# Sheet_1_2023-07-02.net
KiCad netlist of a schematic drawn in Altium Designer
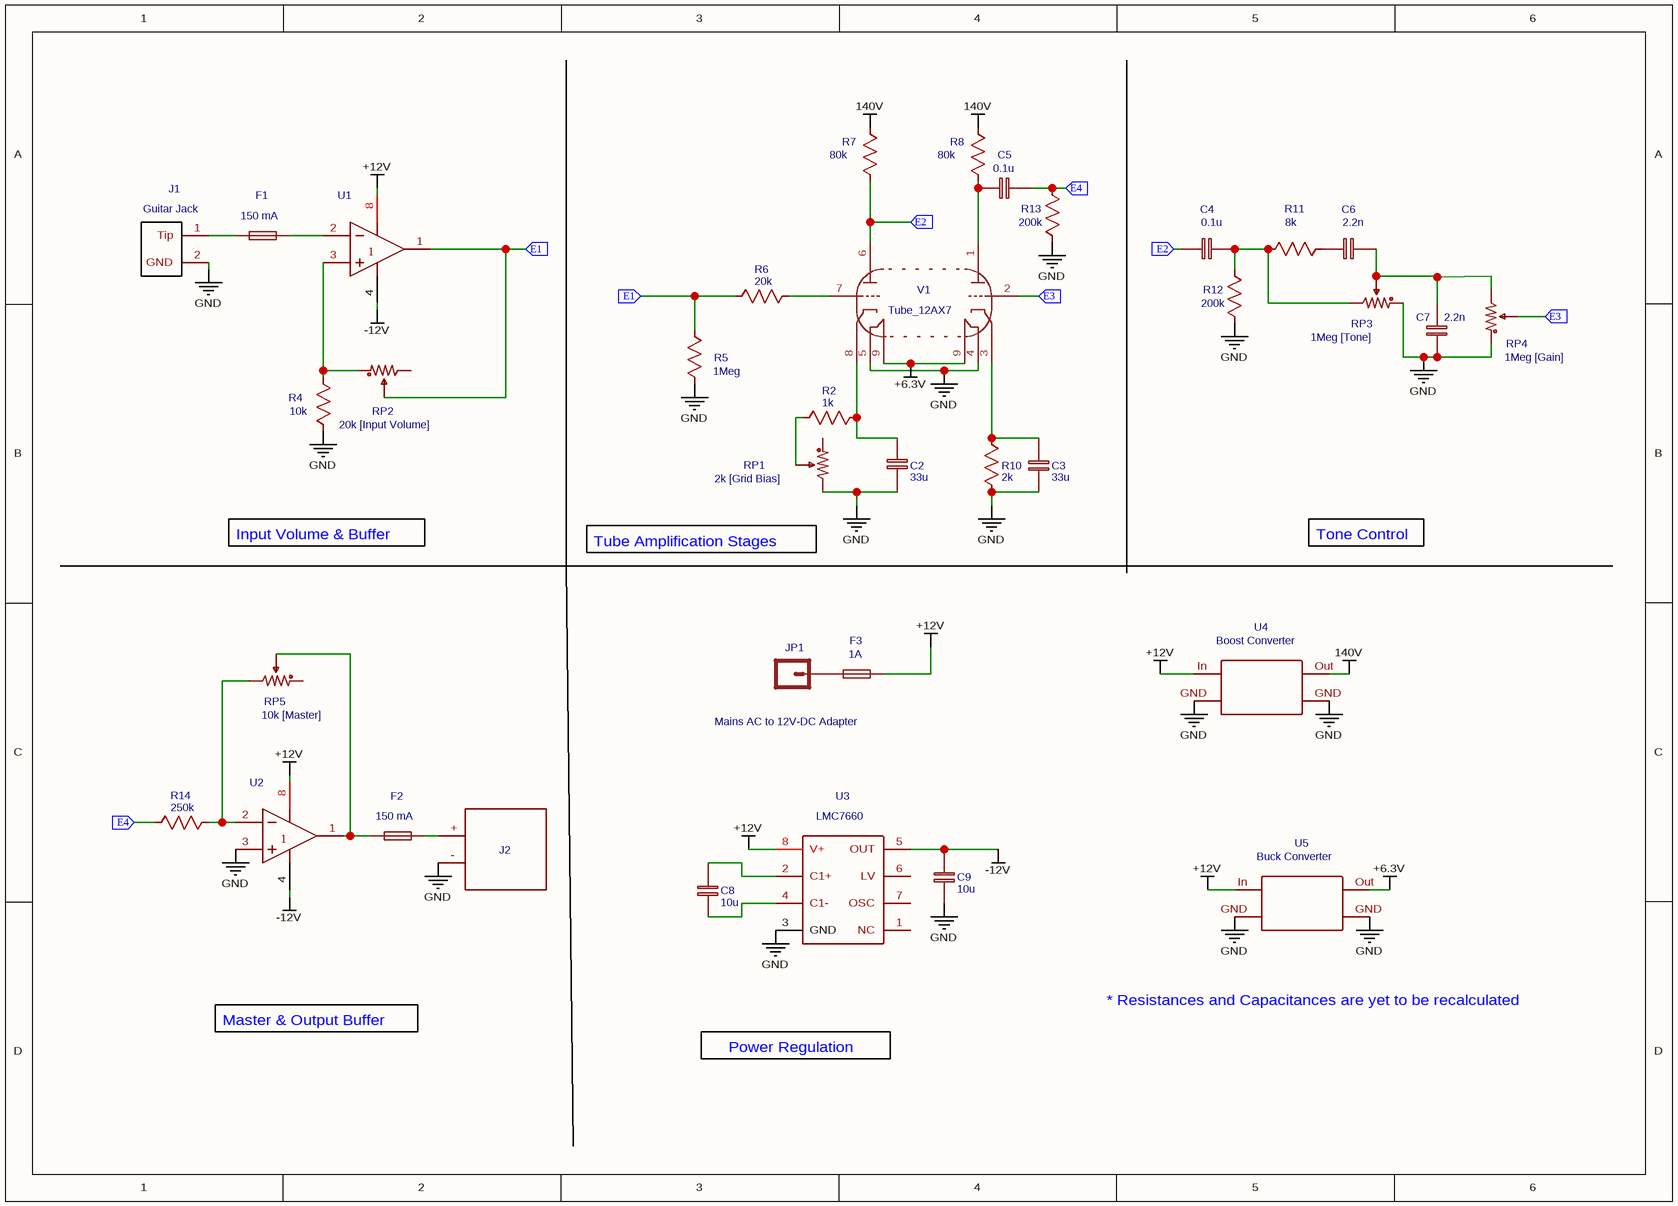
[diagram p0: Sheet_1_2023-07-02.schdoc]

(export (version "E")
  (design (tool "Eeschema 10.0.6"))
  (components
    (comp (ref "C2")
      (value "33u")
      (fields (field (name "CONTRIBUTOR") "LCEDA_Lib"))
      (libsource (lib "altium-import") (part "root_3_33u_"))
    )
    (comp (ref "C3")
      (value "33u")
      (fields (field (name "CONTRIBUTOR") "LCEDA_Lib"))
      (libsource (lib "altium-import") (part "root_1_33u_"))
    )
    (comp (ref "C4")
      (value "0.1u")
      (fields (field (name "CONTRIBUTOR") "LCEDA_Lib"))
      (libsource (lib "altium-import") (part "root_0_0.1u_"))
    )
    (comp (ref "C5")
      (value "0.1u")
      (fields (field (name "CONTRIBUTOR") "LCEDA_Lib"))
      (libsource (lib "altium-import") (part "root_0_0.1u_"))
    )
    (comp (ref "C6")
      (value "2.2n")
      (fields (field (name "CONTRIBUTOR") "LCEDA_Lib"))
      (libsource (lib "altium-import") (part "root_0_2.2n_"))
    )
    (comp (ref "C7")
      (value "2.2n")
      (fields (field (name "CONTRIBUTOR") "LCEDA_Lib"))
      (libsource (lib "altium-import") (part "root_1_2.2n_"))
    )
    (comp (ref "C8")
      (value "10u")
      (fields (field (name "CONTRIBUTOR") "LCEDA_Lib"))
      (libsource (lib "altium-import") (part "root_1_10u_"))
    )
    (comp (ref "C9")
      (value "10u")
      (fields (field (name "CONTRIBUTOR") "LCEDA_Lib"))
      (libsource (lib "altium-import") (part "root_1_10u_"))
    )
    (comp (ref "F1") (value "150 mA") (libsource (lib "altium-import") (part "root_0_150 mA_")))
    (comp (ref "F2") (value "150 mA") (libsource (lib "altium-import") (part "root_0_150 mA_")))
    (comp (ref "F3") (value "1A") (libsource (lib "altium-import") (part "root_0_1A_")))
    (comp (ref "J1")
      (value "Guitar Jack")
      (fields (field (name "CONTRIBUTOR") "Jose Tovar"))
      (libsource (lib "altium-import") (part "root_0_Guitar Jack_"))
    )
    (comp (ref "J2")
      (value "Guitar_Jack_Output")
      (fields (field (name "CONTRIBUTOR") "ahmits"))
      (libsource (lib "altium-import") (part "root_0_Guitar_Jack_Output_"))
    )
    (comp (ref "JP1")
      (value "Mains AC to 12V-DC Adapter")
      (fields (field (name "CONTRIBUTOR") "SparkFun"))
      (libsource (lib "altium-import") (part "root_0_Mains AC to 12V-DC Adapter_"))
    )
    (comp (ref "R2")
      (value "1k")
      (fields (field (name "CONTRIBUTOR") "LCEDA_Lib"))
      (libsource (lib "altium-import") (part "root_2_1k_"))
    )
    (comp (ref "R4")
      (value "10k")
      (fields (field (name "CONTRIBUTOR") "LCEDA_Lib"))
      (libsource (lib "altium-import") (part "root_1_10k_"))
    )
    (comp (ref "R5")
      (value "1Meg")
      (fields (field (name "CONTRIBUTOR") "LCEDA_Lib"))
      (libsource (lib "altium-import") (part "root_1_1Meg_"))
    )
    (comp (ref "R6")
      (value "20k")
      (fields (field (name "CONTRIBUTOR") "LCEDA_Lib"))
      (libsource (lib "altium-import") (part "root_2_20k_"))
    )
    (comp (ref "R7")
      (value "80k")
      (fields (field (name "CONTRIBUTOR") "LCEDA_Lib"))
      (libsource (lib "altium-import") (part "root_3_80k_"))
    )
    (comp (ref "R8")
      (value "80k")
      (fields (field (name "CONTRIBUTOR") "LCEDA_Lib"))
      (libsource (lib "altium-import") (part "root_3_80k_"))
    )
    (comp (ref "R10")
      (value "2k")
      (fields (field (name "CONTRIBUTOR") "LCEDA_Lib"))
      (libsource (lib "altium-import") (part "root_3_2k_"))
    )
    (comp (ref "R11")
      (value "8k")
      (fields (field (name "CONTRIBUTOR") "LCEDA_Lib"))
      (libsource (lib "altium-import") (part "root_2_8k_"))
    )
    (comp (ref "R12")
      (value "200k")
      (fields (field (name "CONTRIBUTOR") "LCEDA_Lib"))
      (libsource (lib "altium-import") (part "root_3_200k_"))
    )
    (comp (ref "R13")
      (value "200k")
      (fields (field (name "CONTRIBUTOR") "LCEDA_Lib"))
      (libsource (lib "altium-import") (part "root_3_200k_"))
    )
    (comp (ref "R14")
      (value "250k")
      (fields (field (name "CONTRIBUTOR") "LCEDA_Lib"))
      (libsource (lib "altium-import") (part "root_2_250k_"))
    )
    (comp (ref "RP1")
      (value "2k [Grid Bias]")
      (fields (field (name "CONTRIBUTOR") "LCEDA_Lib"))
      (libsource (lib "altium-import") (part "root_1_2k [Grid Bias]_"))
    )
    (comp (ref "RP2")
      (value "20k [Input Volume]")
      (fields (field (name "CONTRIBUTOR") "LCEDA_Lib"))
      (libsource (lib "altium-import") (part "root_2_20k [Input Volume]_"))
    )
    (comp (ref "RP3")
      (value "1Meg [Tone]")
      (fields (field (name "CONTRIBUTOR") "LCEDA_Lib"))
      (libsource (lib "altium-import") (part "root_0_1Meg [Tone]_"))
    )
    (comp (ref "RP4")
      (value "1Meg [Gain]")
      (fields (field (name "CONTRIBUTOR") "LCEDA_Lib"))
      (libsource (lib "altium-import") (part "root_3_1Meg [Gain]_"))
    )
    (comp (ref "RP5")
      (value "10k [Master]")
      (fields (field (name "CONTRIBUTOR") "LCEDA_Lib"))
      (libsource (lib "altium-import") (part "root_0_10k [Master]_"))
    )
    (comp (ref "U1")
      (value "HA7-5102-2")
      (description "Low Noise Operational Amplifier")
      (fields (field (name "SUBPART_NO") "1"))
      (libsource (lib "altium-import") (part "root_0_HA7-5102-2_"))
    )
    (comp (ref "U2")
      (value "HA7-5102-2")
      (description "Low Noise Operational Amplifier")
      (fields (field (name "SUBPART_NO") "1"))
      (libsource (lib "altium-import") (part "root_0_HA7-5102-2_"))
    )
    (comp (ref "U3")
      (value "LMC7660")
      (description "Switched Capacitor Voltage Converter, 8-pin MDIP, Pb-Free")
      (libsource (lib "altium-import") (part "root_0_LMC7660_"))
    )
    (comp (ref "U4")
      (value "Boost Converter")
      (description "800mA Low-Dropout Linear Regulator, 4-pin SOT-223, Pb-Free")
      (libsource (lib "altium-import") (part "root_0_Boost Converter_"))
    )
    (comp (ref "U5")
      (value "Buck Converter")
      (description "800mA Low-Dropout Linear Regulator, 4-pin SOT-223, Pb-Free")
      (libsource (lib "altium-import") (part "root_0_Buck Converter_"))
    )
    (comp (ref "V1")
      (value "Tube_12AX7")
      (description "High Mu Dual Triode")
      (fields (field (name "CONTRIBUTOR") "prvi sedmi"))
      (libsource (lib "altium-import") (part "root_0_Tube_12AX7_"))
    )
  )
  (nets
    (net (code "1") (name "+6.3V") (class "Default")
      (node (ref "U5") (pin "Out") (pinfunction "OUT_Out") (pintype "passive"))
      (node (ref "V1") (pin "9") (pinfunction "HM_9") (pintype "passive"))
    )
    (net (code "2") (name "+12V") (class "Default")
      (node (ref "F3") (pin "2") (pinfunction "2_2") (pintype "passive"))
      (node (ref "U1") (pin "8") (pinfunction "V+_8") (pintype "passive"))
      (node (ref "U2") (pin "8") (pinfunction "V+_8") (pintype "passive"))
      (node (ref "U3") (pin "8") (pinfunction "V+_8") (pintype "passive"))
      (node (ref "U4") (pin "In") (pinfunction "IN_In") (pintype "passive"))
      (node (ref "U5") (pin "In") (pinfunction "IN_In") (pintype "passive"))
    )
    (net (code "3") (name "-12V") (class "Default")
      (node (ref "C9") (pin "2") (pinfunction "2_2") (pintype "passive"))
      (node (ref "U1") (pin "4") (pinfunction "V-_4") (pintype "passive"))
      (node (ref "U2") (pin "4") (pinfunction "V-_4") (pintype "passive"))
      (node (ref "U3") (pin "5") (pinfunction "OUT_5") (pintype "passive"))
    )
    (net (code "4") (name "/E1") (class "Default")
      (node (ref "R5") (pin "2") (pinfunction "2_2") (pintype "passive"))
      (node (ref "R6") (pin "2") (pinfunction "2_2") (pintype "passive"))
      (node (ref "RP2") (pin "2") (pinfunction "2_2") (pintype "passive"))
      (node (ref "U1") (pin "1") (pinfunction "OUT_1") (pintype "passive"))
    )
    (net (code "5") (name "/E2") (class "Default")
      (node (ref "C4") (pin "1") (pinfunction "1_1") (pintype "passive"))
      (node (ref "R7") (pin "2") (pinfunction "2_2") (pintype "passive"))
      (node (ref "V1") (pin "6") (pinfunction "PT2_6") (pintype "passive"))
    )
    (net (code "6") (name "/E3") (class "Default")
      (node (ref "RP4") (pin "2") (pinfunction "2_2") (pintype "passive"))
      (node (ref "V1") (pin "2") (pinfunction "GT1_2") (pintype "passive"))
    )
    (net (code "7") (name "/E4") (class "Default")
      (node (ref "C5") (pin "2") (pinfunction "2_2") (pintype "passive"))
      (node (ref "R13") (pin "1") (pinfunction "1_1") (pintype "passive"))
      (node (ref "R14") (pin "2") (pinfunction "2_2") (pintype "passive"))
    )
    (net (code "8") (name "140V") (class "Default")
      (node (ref "R7") (pin "1") (pinfunction "1_1") (pintype "passive"))
      (node (ref "R8") (pin "1") (pinfunction "1_1") (pintype "passive"))
      (node (ref "U4") (pin "Out") (pinfunction "OUT_Out") (pintype "passive"))
    )
    (net (code "9") (name "GND") (class "Default")
      (node (ref "C2") (pin "2") (pinfunction "2_2") (pintype "passive"))
      (node (ref "C3") (pin "1") (pinfunction "1_1") (pintype "passive"))
      (node (ref "C7") (pin "1") (pinfunction "1_1") (pintype "passive"))
      (node (ref "C9") (pin "1") (pinfunction "1_1") (pintype "passive"))
      (node (ref "J1") (pin "2") (pinfunction "GND_2") (pintype "passive"))
      (node (ref "R10") (pin "2") (pinfunction "2_2") (pintype "passive"))
      (node (ref "R12") (pin "2") (pinfunction "2_2") (pintype "passive"))
      (node (ref "R13") (pin "2") (pinfunction "2_2") (pintype "passive"))
      (node (ref "R4") (pin "1") (pinfunction "1_1") (pintype "passive"))
      (node (ref "R5") (pin "1") (pinfunction "1_1") (pintype "passive"))
      (node (ref "RP1") (pin "3") (pinfunction "3_3") (pintype "passive"))
      (node (ref "RP3") (pin "1") (pinfunction "1_1") (pintype "passive"))
      (node (ref "RP4") (pin "1") (pinfunction "1_1") (pintype "passive"))
      (node (ref "U2") (pin "3") (pinfunction "IN+_3") (pintype "passive"))
      (node (ref "U3") (pin "3") (pinfunction "GND_3") (pintype "passive"))
      (node (ref "U4") (pin "GND") (pinfunction "ADJ_GND") (pintype "passive"))
      (node (ref "U5") (pin "GND") (pinfunction "TAB_GND") (pintype "passive"))
      (node (ref "V1") (pin "4") (pinfunction "H_4") (pintype "passive"))
      (node (ref "V1") (pin "5") (pinfunction "H_5") (pintype "passive"))
    )
    (net (code "10") (name "Net-(C4-Pad2)") (class "Default")
      (node (ref "C4") (pin "2") (pinfunction "2_2") (pintype "passive"))
      (node (ref "R11") (pin "2") (pinfunction "2_2") (pintype "passive"))
      (node (ref "R12") (pin "1") (pinfunction "1_1") (pintype "passive"))
      (node (ref "RP3") (pin "3") (pinfunction "3_3") (pintype "passive"))
    )
    (net (code "11") (name "Net-(C6-Pad1)") (class "Default")
      (node (ref "C6") (pin "1") (pinfunction "1_1") (pintype "passive"))
      (node (ref "R11") (pin "1") (pinfunction "1_1") (pintype "passive"))
    )
    (net (code "12") (name "Net-(C6-Pad2)") (class "Default")
      (node (ref "C6") (pin "2") (pinfunction "2_2") (pintype "passive"))
      (node (ref "C7") (pin "2") (pinfunction "2_2") (pintype "passive"))
      (node (ref "RP3") (pin "2") (pinfunction "2_2") (pintype "passive"))
      (node (ref "RP4") (pin "3") (pinfunction "3_3") (pintype "passive"))
    )
    (net (code "13") (name "Net-(J1-Tip)") (class "Default")
      (node (ref "F1") (pin "1") (pinfunction "1_1") (pintype "passive"))
      (node (ref "J1") (pin "1") (pinfunction "Tip_1") (pintype "passive"))
    )
    (net (code "14") (name "Net-(JP1-1)") (class "Default")
      (node (ref "F3") (pin "1") (pinfunction "1_1") (pintype "passive"))
      (node (ref "JP1") (pin "P$2") (pinfunction "1_P$2") (pintype "passive"))
    )
    (net (code "15") (name "Net-(R2-Pad2)") (class "Default")
      (node (ref "R2") (pin "2") (pinfunction "2_2") (pintype "passive"))
      (node (ref "RP1") (pin "2") (pinfunction "2_2") (pintype "passive"))
    )
    (net (code "16") (name "Net-(U1-IN+)") (class "Default")
      (node (ref "R4") (pin "2") (pinfunction "2_2") (pintype "passive"))
      (node (ref "RP2") (pin "1") (pinfunction "1_1") (pintype "passive"))
      (node (ref "U1") (pin "3") (pinfunction "IN+_3") (pintype "passive"))
    )
    (net (code "17") (name "Net-(U1-IN-)") (class "Default")
      (node (ref "F1") (pin "2") (pinfunction "2_2") (pintype "passive"))
      (node (ref "U1") (pin "2") (pinfunction "IN-_2") (pintype "passive"))
    )
    (net (code "18") (name "Net-(U2-IN-)") (class "Default")
      (node (ref "R14") (pin "1") (pinfunction "1_1") (pintype "passive"))
      (node (ref "RP5") (pin "3") (pinfunction "3_3") (pintype "passive"))
      (node (ref "U2") (pin "2") (pinfunction "IN-_2") (pintype "passive"))
    )
    (net (code "19") (name "Net-(U2-OUT)") (class "Default")
      (node (ref "F2") (pin "1") (pinfunction "1_1") (pintype "passive"))
      (node (ref "RP5") (pin "2") (pinfunction "2_2") (pintype "passive"))
      (node (ref "U2") (pin "1") (pinfunction "OUT_1") (pintype "passive"))
    )
    (net (code "20") (name "Net-(U3-C1+)") (class "Default")
      (node (ref "C8") (pin "2") (pinfunction "2_2") (pintype "passive"))
      (node (ref "U3") (pin "2") (pinfunction "C1+_2") (pintype "passive"))
    )
    (net (code "21") (name "Net-(U3-C1-)") (class "Default")
      (node (ref "C8") (pin "1") (pinfunction "1_1") (pintype "passive"))
      (node (ref "U3") (pin "4") (pinfunction "C1-_4") (pintype "passive"))
    )
    (net (code "22") (name "Net-(V1-GT2)") (class "Default")
      (node (ref "R6") (pin "1") (pinfunction "1_1") (pintype "passive"))
      (node (ref "V1") (pin "7") (pinfunction "GT2_7") (pintype "passive"))
    )
    (net (code "23") (name "Net-(V1-KT1)") (class "Default")
      (node (ref "C3") (pin "2") (pinfunction "2_2") (pintype "passive"))
      (node (ref "R10") (pin "1") (pinfunction "1_1") (pintype "passive"))
      (node (ref "V1") (pin "3") (pinfunction "KT1_3") (pintype "passive"))
    )
    (net (code "24") (name "Net-(V1-KT2)") (class "Default")
      (node (ref "C2") (pin "1") (pinfunction "1_1") (pintype "passive"))
      (node (ref "R2") (pin "1") (pinfunction "1_1") (pintype "passive"))
      (node (ref "V1") (pin "8") (pinfunction "KT2_8") (pintype "passive"))
    )
    (net (code "25") (name "Net-(V1-PT1)") (class "Default")
      (node (ref "C5") (pin "1") (pinfunction "1_1") (pintype "passive"))
      (node (ref "R8") (pin "2") (pinfunction "2_2") (pintype "passive"))
      (node (ref "V1") (pin "1") (pinfunction "PT1_1") (pintype "passive"))
    )
    (net (code "26") (name "unconnected-(F2-Pad2)") (class "Default")
      (node (ref "F2") (pin "2") (pinfunction "2_2") (pintype "passive"))
    )
    (net (code "27") (name "unconnected-(J2-1-Pad+)") (class "Default")
      (node (ref "J2") (pin "+") (pinfunction "1_+") (pintype "passive"))
    )
    (net (code "28") (name "unconnected-(J2-2-Pad-)") (class "Default")
      (node (ref "J2") (pin "-") (pinfunction "2_-") (pintype "passive"))
    )
    (net (code "29") (name "unconnected-(RP1-Pad1)") (class "Default")
      (node (ref "RP1") (pin "1") (pinfunction "1_1") (pintype "passive"))
    )
    (net (code "30") (name "unconnected-(RP2-Pad3)") (class "Default")
      (node (ref "RP2") (pin "3") (pinfunction "3_3") (pintype "passive"))
    )
    (net (code "31") (name "unconnected-(RP5-Pad1)") (class "Default")
      (node (ref "RP5") (pin "1") (pinfunction "1_1") (pintype "passive"))
    )
    (net (code "32") (name "unconnected-(U3-LV-Pad6)") (class "Default")
      (node (ref "U3") (pin "6") (pinfunction "LV_6") (pintype "passive"))
    )
    (net (code "33") (name "unconnected-(U3-NC-Pad1)") (class "Default")
      (node (ref "U3") (pin "1") (pinfunction "NC_1") (pintype "passive"))
    )
    (net (code "34") (name "unconnected-(U3-OSC-Pad7)") (class "Default")
      (node (ref "U3") (pin "7") (pinfunction "OSC_7") (pintype "passive"))
    )
  )
)
